# IMU.net
KiCad netlist of a schematic drawn in Altium Designer
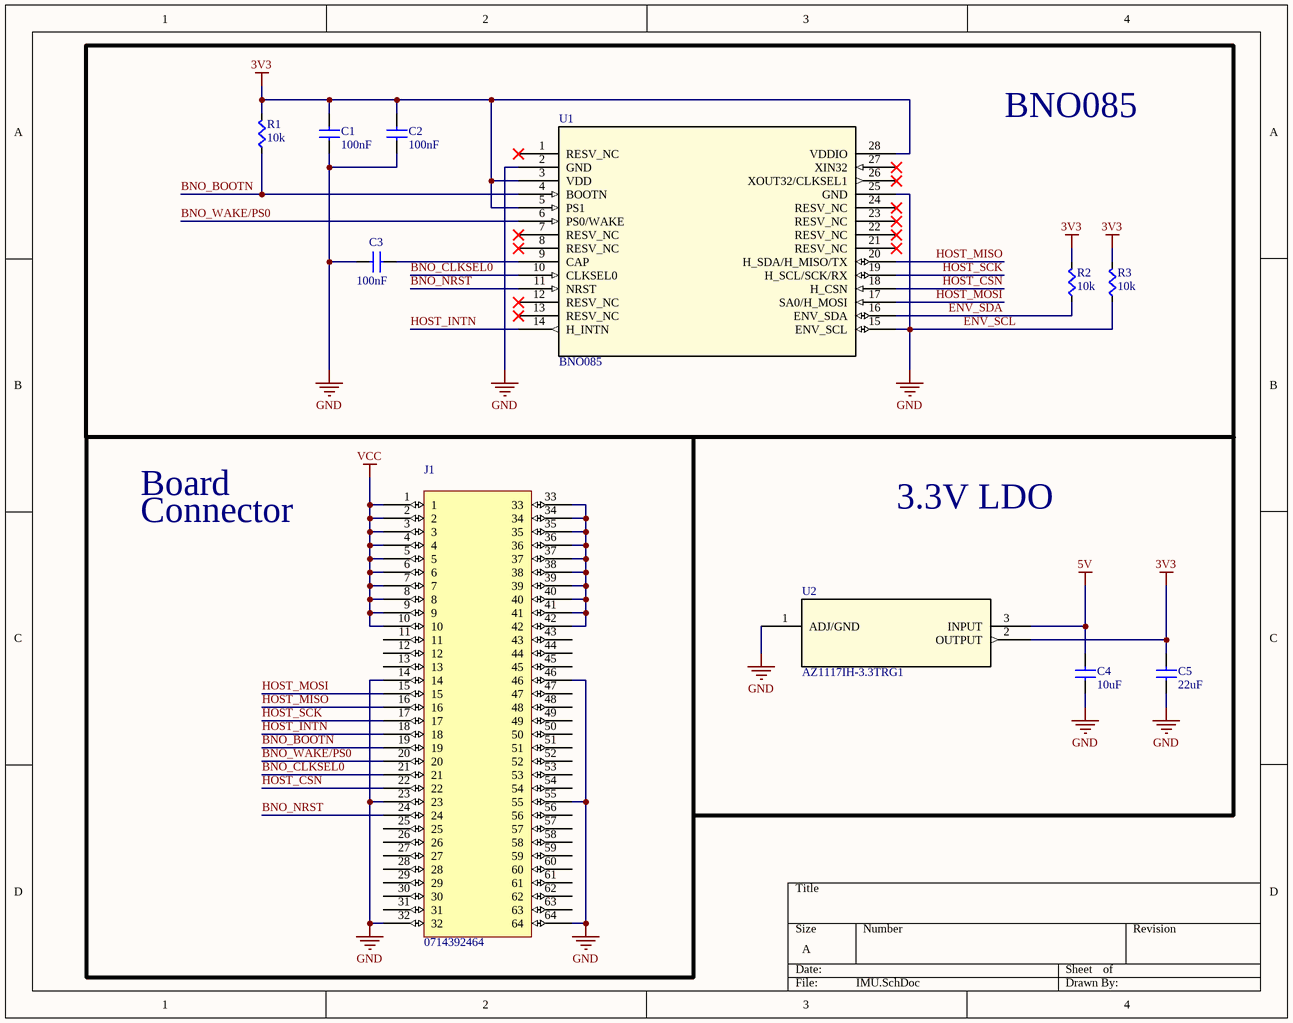
[diagram p0: IMU.SchDoc]

(export (version "E")
  (design (tool "Eeschema 10.0.6"))
  (components
    (comp (ref "C1")
      (value "100nF")
      (footprint "CAPC0603")
      (fields (field (name "Comment") "Cap"))
      (libsource (lib "Passives") (part "Cap"))
    )
    (comp (ref "C2")
      (value "100nF")
      (footprint "CAPC0603")
      (fields (field (name "Comment") "Cap"))
      (libsource (lib "Passives") (part "Cap"))
    )
    (comp (ref "C3")
      (value "100nF")
      (footprint "CAPC0603")
      (fields (field (name "Comment") "Cap"))
      (libsource (lib "Passives") (part "Cap"))
    )
    (comp (ref "C4")
      (value "10uF")
      (footprint "CAPC0805")
      (fields (field (name "Comment") "Cap"))
      (libsource (lib "Passives") (part "Cap"))
    )
    (comp (ref "C5")
      (value "22uF")
      (footprint "CAPC0603")
      (fields (field (name "Comment") "Cap"))
      (libsource (lib "Passives") (part "Cap"))
    )
    (comp (ref "J1")
      (value "0714392464")
      (footprint "0714392464")
      (description "64 Position Connector Receptacle, Outer Shroud Contacts Surface Mount Gold")
      (libsource (lib "Connectors") (part "0714392464"))
    )
    (comp (ref "R1")
      (value "10k")
      (footprint "RES0603")
      (fields (field (name "Comment") "Res"))
      (libsource (lib "Passives") (part "Res"))
    )
    (comp (ref "R2")
      (value "10k")
      (footprint "RES0603")
      (fields (field (name "Comment") "Res"))
      (libsource (lib "Passives") (part "Res"))
    )
    (comp (ref "R3")
      (value "10k")
      (footprint "RES0603")
      (fields (field (name "Comment") "Res"))
      (libsource (lib "Passives") (part "Res"))
    )
    (comp (ref "U1")
      (value "BNO085")
      (footprint "LGA28_5.2X3.8_CEV")
      (description "No Description Available")
      (fields (field (name "COPYRIGHT") "Copyright (C) 2023 Ultra Librarian. All rights reserved."))
      (libsource (lib "ICs") (part "BNO085"))
    )
    (comp (ref "U2")
      (value "AZ1117IH-3.3TRG1")
      (footprint "SOT223_AZ1117I_6P5X3P5_DIO")
      (description "No Description Available")
      (fields (field (name "COPYRIGHT") "Copyright (C) 2023 Ultra Librarian. All rights reserved."))
      (libsource (lib "ICs") (part "AZ1117IH-3.3TRG1"))
    )
  )
  (nets
    (net (code "1") (name "/BNO_BOOTN") (class "Default")
      (node (ref "J1") (pin "19") (pinfunction "19_19") (pintype "bidirectional"))
      (node (ref "R1") (pin "2") (pinfunction "B_2") (pintype "passive"))
      (node (ref "U1") (pin "4") (pinfunction "BOOTN_4") (pintype "input"))
    )
    (net (code "2") (name "/BNO_CLKSEL0") (class "Default")
      (node (ref "J1") (pin "21") (pinfunction "21_21") (pintype "bidirectional"))
      (node (ref "U1") (pin "10") (pinfunction "CLKSEL0_10") (pintype "input"))
    )
    (net (code "3") (name "/BNO_NRST") (class "Default")
      (node (ref "J1") (pin "24") (pinfunction "24_24") (pintype "bidirectional"))
      (node (ref "U1") (pin "11") (pinfunction "NRST_11") (pintype "input"))
    )
    (net (code "4") (name "/BNO_WAKE{slash}PS0") (class "Default")
      (node (ref "J1") (pin "20") (pinfunction "20_20") (pintype "bidirectional"))
      (node (ref "U1") (pin "6") (pinfunction "PS0/WAKE_6") (pintype "input"))
    )
    (net (code "5") (name "/ENV_SDA") (class "Default")
      (node (ref "R2") (pin "2") (pinfunction "B_2") (pintype "passive"))
      (node (ref "U1") (pin "16") (pinfunction "ENV_SDA_16") (pintype "bidirectional"))
    )
    (net (code "6") (name "/HOST_CSN") (class "Default")
      (node (ref "J1") (pin "22") (pinfunction "22_22") (pintype "bidirectional"))
      (node (ref "U1") (pin "18") (pinfunction "H_CSN_18") (pintype "input"))
    )
    (net (code "7") (name "/HOST_INTN") (class "Default")
      (node (ref "J1") (pin "18") (pinfunction "18_18") (pintype "bidirectional"))
      (node (ref "U1") (pin "14") (pinfunction "H_INTN_14") (pintype "output"))
    )
    (net (code "8") (name "/HOST_MISO") (class "Default")
      (node (ref "J1") (pin "16") (pinfunction "16_16") (pintype "bidirectional"))
      (node (ref "U1") (pin "20") (pinfunction "H_SDA/H_MISO/TX_20") (pintype "bidirectional"))
    )
    (net (code "9") (name "/HOST_MOSI") (class "Default")
      (node (ref "J1") (pin "15") (pinfunction "15_15") (pintype "bidirectional"))
      (node (ref "U1") (pin "17") (pinfunction "SA0/H_MOSI_17") (pintype "input"))
    )
    (net (code "10") (name "/HOST_SCK") (class "Default")
      (node (ref "J1") (pin "17") (pinfunction "17_17") (pintype "bidirectional"))
      (node (ref "U1") (pin "19") (pinfunction "H_SCL/SCK/RX_19") (pintype "bidirectional"))
    )
    (net (code "11") (name "3V3") (class "Default")
      (node (ref "C1") (pin "1") (pinfunction "A_1") (pintype "passive"))
      (node (ref "C2") (pin "1") (pinfunction "A_1") (pintype "passive"))
      (node (ref "C5") (pin "1") (pinfunction "A_1") (pintype "passive"))
      (node (ref "R1") (pin "1") (pinfunction "A_1") (pintype "passive"))
      (node (ref "R2") (pin "1") (pinfunction "A_1") (pintype "passive"))
      (node (ref "R3") (pin "1") (pinfunction "A_1") (pintype "passive"))
      (node (ref "U1") (pin "28") (pinfunction "VDDIO_28") (pintype "power_in"))
      (node (ref "U1") (pin "3") (pinfunction "VDD_3") (pintype "power_in"))
      (node (ref "U1") (pin "5") (pinfunction "PS1_5") (pintype "input"))
      (node (ref "U2") (pin "2") (pinfunction "OUTPUT_2") (pintype "output"))
    )
    (net (code "12") (name "5V") (class "Default")
      (node (ref "C4") (pin "1") (pinfunction "A_1") (pintype "passive"))
      (node (ref "U2") (pin "3") (pinfunction "INPUT_3") (pintype "passive"))
    )
    (net (code "13") (name "GND") (class "Default")
      (node (ref "C1") (pin "2") (pinfunction "B_2") (pintype "passive"))
      (node (ref "C2") (pin "2") (pinfunction "B_2") (pintype "passive"))
      (node (ref "C3") (pin "1") (pinfunction "A_1") (pintype "passive"))
      (node (ref "C4") (pin "2") (pinfunction "B_2") (pintype "passive"))
      (node (ref "C5") (pin "2") (pinfunction "B_2") (pintype "passive"))
      (node (ref "J1") (pin "14") (pinfunction "14_14") (pintype "bidirectional"))
      (node (ref "J1") (pin "23") (pinfunction "23_23") (pintype "bidirectional"))
      (node (ref "J1") (pin "32") (pinfunction "32_32") (pintype "bidirectional"))
      (node (ref "J1") (pin "46") (pinfunction "46_46") (pintype "bidirectional"))
      (node (ref "J1") (pin "55") (pinfunction "55_55") (pintype "bidirectional"))
      (node (ref "J1") (pin "64") (pinfunction "64_64") (pintype "bidirectional"))
      (node (ref "R3") (pin "2") (pinfunction "B_2") (pintype "passive"))
      (node (ref "U1") (pin "15") (pinfunction "ENV_SCL_15") (pintype "bidirectional"))
      (node (ref "U1") (pin "2") (pinfunction "GND_2") (pintype "passive"))
      (node (ref "U1") (pin "25") (pinfunction "GND_25") (pintype "passive"))
      (node (ref "U2") (pin "1") (pinfunction "ADJ/GND_1") (pintype "passive"))
    )
    (net (code "14") (name "Net-(C3-B)") (class "Default")
      (node (ref "C3") (pin "2") (pinfunction "B_2") (pintype "passive"))
      (node (ref "U1") (pin "9") (pinfunction "CAP_9") (pintype "power_in"))
    )
    (net (code "15") (name "Net-(J1-Pad33)") (class "Default")
      (node (ref "J1") (pin "33") (pinfunction "33_33") (pintype "bidirectional"))
      (node (ref "J1") (pin "34") (pinfunction "34_34") (pintype "bidirectional"))
      (node (ref "J1") (pin "35") (pinfunction "35_35") (pintype "bidirectional"))
      (node (ref "J1") (pin "36") (pinfunction "36_36") (pintype "bidirectional"))
      (node (ref "J1") (pin "37") (pinfunction "37_37") (pintype "bidirectional"))
      (node (ref "J1") (pin "38") (pinfunction "38_38") (pintype "bidirectional"))
      (node (ref "J1") (pin "39") (pinfunction "39_39") (pintype "bidirectional"))
      (node (ref "J1") (pin "40") (pinfunction "40_40") (pintype "bidirectional"))
      (node (ref "J1") (pin "41") (pinfunction "41_41") (pintype "bidirectional"))
      (node (ref "J1") (pin "42") (pinfunction "42_42") (pintype "bidirectional"))
    )
    (net (code "16") (name "VCC") (class "Default")
      (node (ref "J1") (pin "1") (pinfunction "1_1") (pintype "bidirectional"))
      (node (ref "J1") (pin "10") (pinfunction "10_10") (pintype "bidirectional"))
      (node (ref "J1") (pin "2") (pinfunction "2_2") (pintype "bidirectional"))
      (node (ref "J1") (pin "3") (pinfunction "3_3") (pintype "bidirectional"))
      (node (ref "J1") (pin "4") (pinfunction "4_4") (pintype "bidirectional"))
      (node (ref "J1") (pin "5") (pinfunction "5_5") (pintype "bidirectional"))
      (node (ref "J1") (pin "6") (pinfunction "6_6") (pintype "bidirectional"))
      (node (ref "J1") (pin "7") (pinfunction "7_7") (pintype "bidirectional"))
      (node (ref "J1") (pin "8") (pinfunction "8_8") (pintype "bidirectional"))
      (node (ref "J1") (pin "9") (pinfunction "9_9") (pintype "bidirectional"))
    )
    (net (code "17") (name "unconnected-(J1-Pad11)") (class "Default")
      (node (ref "J1") (pin "11") (pinfunction "11_11") (pintype "bidirectional"))
    )
    (net (code "18") (name "unconnected-(J1-Pad12)") (class "Default")
      (node (ref "J1") (pin "12") (pinfunction "12_12") (pintype "bidirectional"))
    )
    (net (code "19") (name "unconnected-(J1-Pad13)") (class "Default")
      (node (ref "J1") (pin "13") (pinfunction "13_13") (pintype "bidirectional"))
    )
    (net (code "20") (name "unconnected-(J1-Pad25)") (class "Default")
      (node (ref "J1") (pin "25") (pinfunction "25_25") (pintype "bidirectional"))
    )
    (net (code "21") (name "unconnected-(J1-Pad26)") (class "Default")
      (node (ref "J1") (pin "26") (pinfunction "26_26") (pintype "bidirectional"))
    )
    (net (code "22") (name "unconnected-(J1-Pad27)") (class "Default")
      (node (ref "J1") (pin "27") (pinfunction "27_27") (pintype "bidirectional"))
    )
    (net (code "23") (name "unconnected-(J1-Pad28)") (class "Default")
      (node (ref "J1") (pin "28") (pinfunction "28_28") (pintype "bidirectional"))
    )
    (net (code "24") (name "unconnected-(J1-Pad29)") (class "Default")
      (node (ref "J1") (pin "29") (pinfunction "29_29") (pintype "bidirectional"))
    )
    (net (code "25") (name "unconnected-(J1-Pad30)") (class "Default")
      (node (ref "J1") (pin "30") (pinfunction "30_30") (pintype "bidirectional"))
    )
    (net (code "26") (name "unconnected-(J1-Pad31)") (class "Default")
      (node (ref "J1") (pin "31") (pinfunction "31_31") (pintype "bidirectional"))
    )
    (net (code "27") (name "unconnected-(J1-Pad43)") (class "Default")
      (node (ref "J1") (pin "43") (pinfunction "43_43") (pintype "bidirectional"))
    )
    (net (code "28") (name "unconnected-(J1-Pad44)") (class "Default")
      (node (ref "J1") (pin "44") (pinfunction "44_44") (pintype "bidirectional"))
    )
    (net (code "29") (name "unconnected-(J1-Pad45)") (class "Default")
      (node (ref "J1") (pin "45") (pinfunction "45_45") (pintype "bidirectional"))
    )
    (net (code "30") (name "unconnected-(J1-Pad47)") (class "Default")
      (node (ref "J1") (pin "47") (pinfunction "47_47") (pintype "bidirectional"))
    )
    (net (code "31") (name "unconnected-(J1-Pad48)") (class "Default")
      (node (ref "J1") (pin "48") (pinfunction "48_48") (pintype "bidirectional"))
    )
    (net (code "32") (name "unconnected-(J1-Pad49)") (class "Default")
      (node (ref "J1") (pin "49") (pinfunction "49_49") (pintype "bidirectional"))
    )
    (net (code "33") (name "unconnected-(J1-Pad50)") (class "Default")
      (node (ref "J1") (pin "50") (pinfunction "50_50") (pintype "bidirectional"))
    )
    (net (code "34") (name "unconnected-(J1-Pad51)") (class "Default")
      (node (ref "J1") (pin "51") (pinfunction "51_51") (pintype "bidirectional"))
    )
    (net (code "35") (name "unconnected-(J1-Pad52)") (class "Default")
      (node (ref "J1") (pin "52") (pinfunction "52_52") (pintype "bidirectional"))
    )
    (net (code "36") (name "unconnected-(J1-Pad53)") (class "Default")
      (node (ref "J1") (pin "53") (pinfunction "53_53") (pintype "bidirectional"))
    )
    (net (code "37") (name "unconnected-(J1-Pad54)") (class "Default")
      (node (ref "J1") (pin "54") (pinfunction "54_54") (pintype "bidirectional"))
    )
    (net (code "38") (name "unconnected-(J1-Pad56)") (class "Default")
      (node (ref "J1") (pin "56") (pinfunction "56_56") (pintype "bidirectional"))
    )
    (net (code "39") (name "unconnected-(J1-Pad57)") (class "Default")
      (node (ref "J1") (pin "57") (pinfunction "57_57") (pintype "bidirectional"))
    )
    (net (code "40") (name "unconnected-(J1-Pad58)") (class "Default")
      (node (ref "J1") (pin "58") (pinfunction "58_58") (pintype "bidirectional"))
    )
    (net (code "41") (name "unconnected-(J1-Pad59)") (class "Default")
      (node (ref "J1") (pin "59") (pinfunction "59_59") (pintype "bidirectional"))
    )
    (net (code "42") (name "unconnected-(J1-Pad60)") (class "Default")
      (node (ref "J1") (pin "60") (pinfunction "60_60") (pintype "bidirectional"))
    )
    (net (code "43") (name "unconnected-(J1-Pad61)") (class "Default")
      (node (ref "J1") (pin "61") (pinfunction "61_61") (pintype "bidirectional"))
    )
    (net (code "44") (name "unconnected-(J1-Pad62)") (class "Default")
      (node (ref "J1") (pin "62") (pinfunction "62_62") (pintype "bidirectional"))
    )
    (net (code "45") (name "unconnected-(J1-Pad63)") (class "Default")
      (node (ref "J1") (pin "63") (pinfunction "63_63") (pintype "bidirectional"))
    )
    (net (code "46") (name "unconnected-(U1-RESV_NC-Pad1)") (class "Default")
      (node (ref "U1") (pin "1") (pinfunction "RESV_NC_1") (pintype "passive+no_connect"))
    )
    (net (code "47") (name "unconnected-(U1-RESV_NC-Pad7)") (class "Default")
      (node (ref "U1") (pin "7") (pinfunction "RESV_NC_7") (pintype "passive+no_connect"))
    )
    (net (code "48") (name "unconnected-(U1-RESV_NC-Pad8)") (class "Default")
      (node (ref "U1") (pin "8") (pinfunction "RESV_NC_8") (pintype "passive+no_connect"))
    )
    (net (code "49") (name "unconnected-(U1-RESV_NC-Pad12)") (class "Default")
      (node (ref "U1") (pin "12") (pinfunction "RESV_NC_12") (pintype "passive+no_connect"))
    )
    (net (code "50") (name "unconnected-(U1-RESV_NC-Pad13)") (class "Default")
      (node (ref "U1") (pin "13") (pinfunction "RESV_NC_13") (pintype "passive+no_connect"))
    )
    (net (code "51") (name "unconnected-(U1-RESV_NC-Pad21)") (class "Default")
      (node (ref "U1") (pin "21") (pinfunction "RESV_NC_21") (pintype "passive+no_connect"))
    )
    (net (code "52") (name "unconnected-(U1-RESV_NC-Pad22)") (class "Default")
      (node (ref "U1") (pin "22") (pinfunction "RESV_NC_22") (pintype "passive+no_connect"))
    )
    (net (code "53") (name "unconnected-(U1-RESV_NC-Pad23)") (class "Default")
      (node (ref "U1") (pin "23") (pinfunction "RESV_NC_23") (pintype "passive+no_connect"))
    )
    (net (code "54") (name "unconnected-(U1-RESV_NC-Pad24)") (class "Default")
      (node (ref "U1") (pin "24") (pinfunction "RESV_NC_24") (pintype "passive+no_connect"))
    )
    (net (code "55") (name "unconnected-(U1-XIN32-Pad27)") (class "Default")
      (node (ref "U1") (pin "27") (pinfunction "XIN32_27") (pintype "input+no_connect"))
    )
    (net (code "56") (name "unconnected-(U1-XOUT32{slash}CLKSEL1-Pad26)") (class "Default")
      (node (ref "U1") (pin "26") (pinfunction "XOUT32/CLKSEL1_26") (pintype "output+no_connect"))
    )
  )
)
